# NFC_Business_Card_2024_Jan_06.net
KiCad netlist of a schematic drawn in EasyEDA
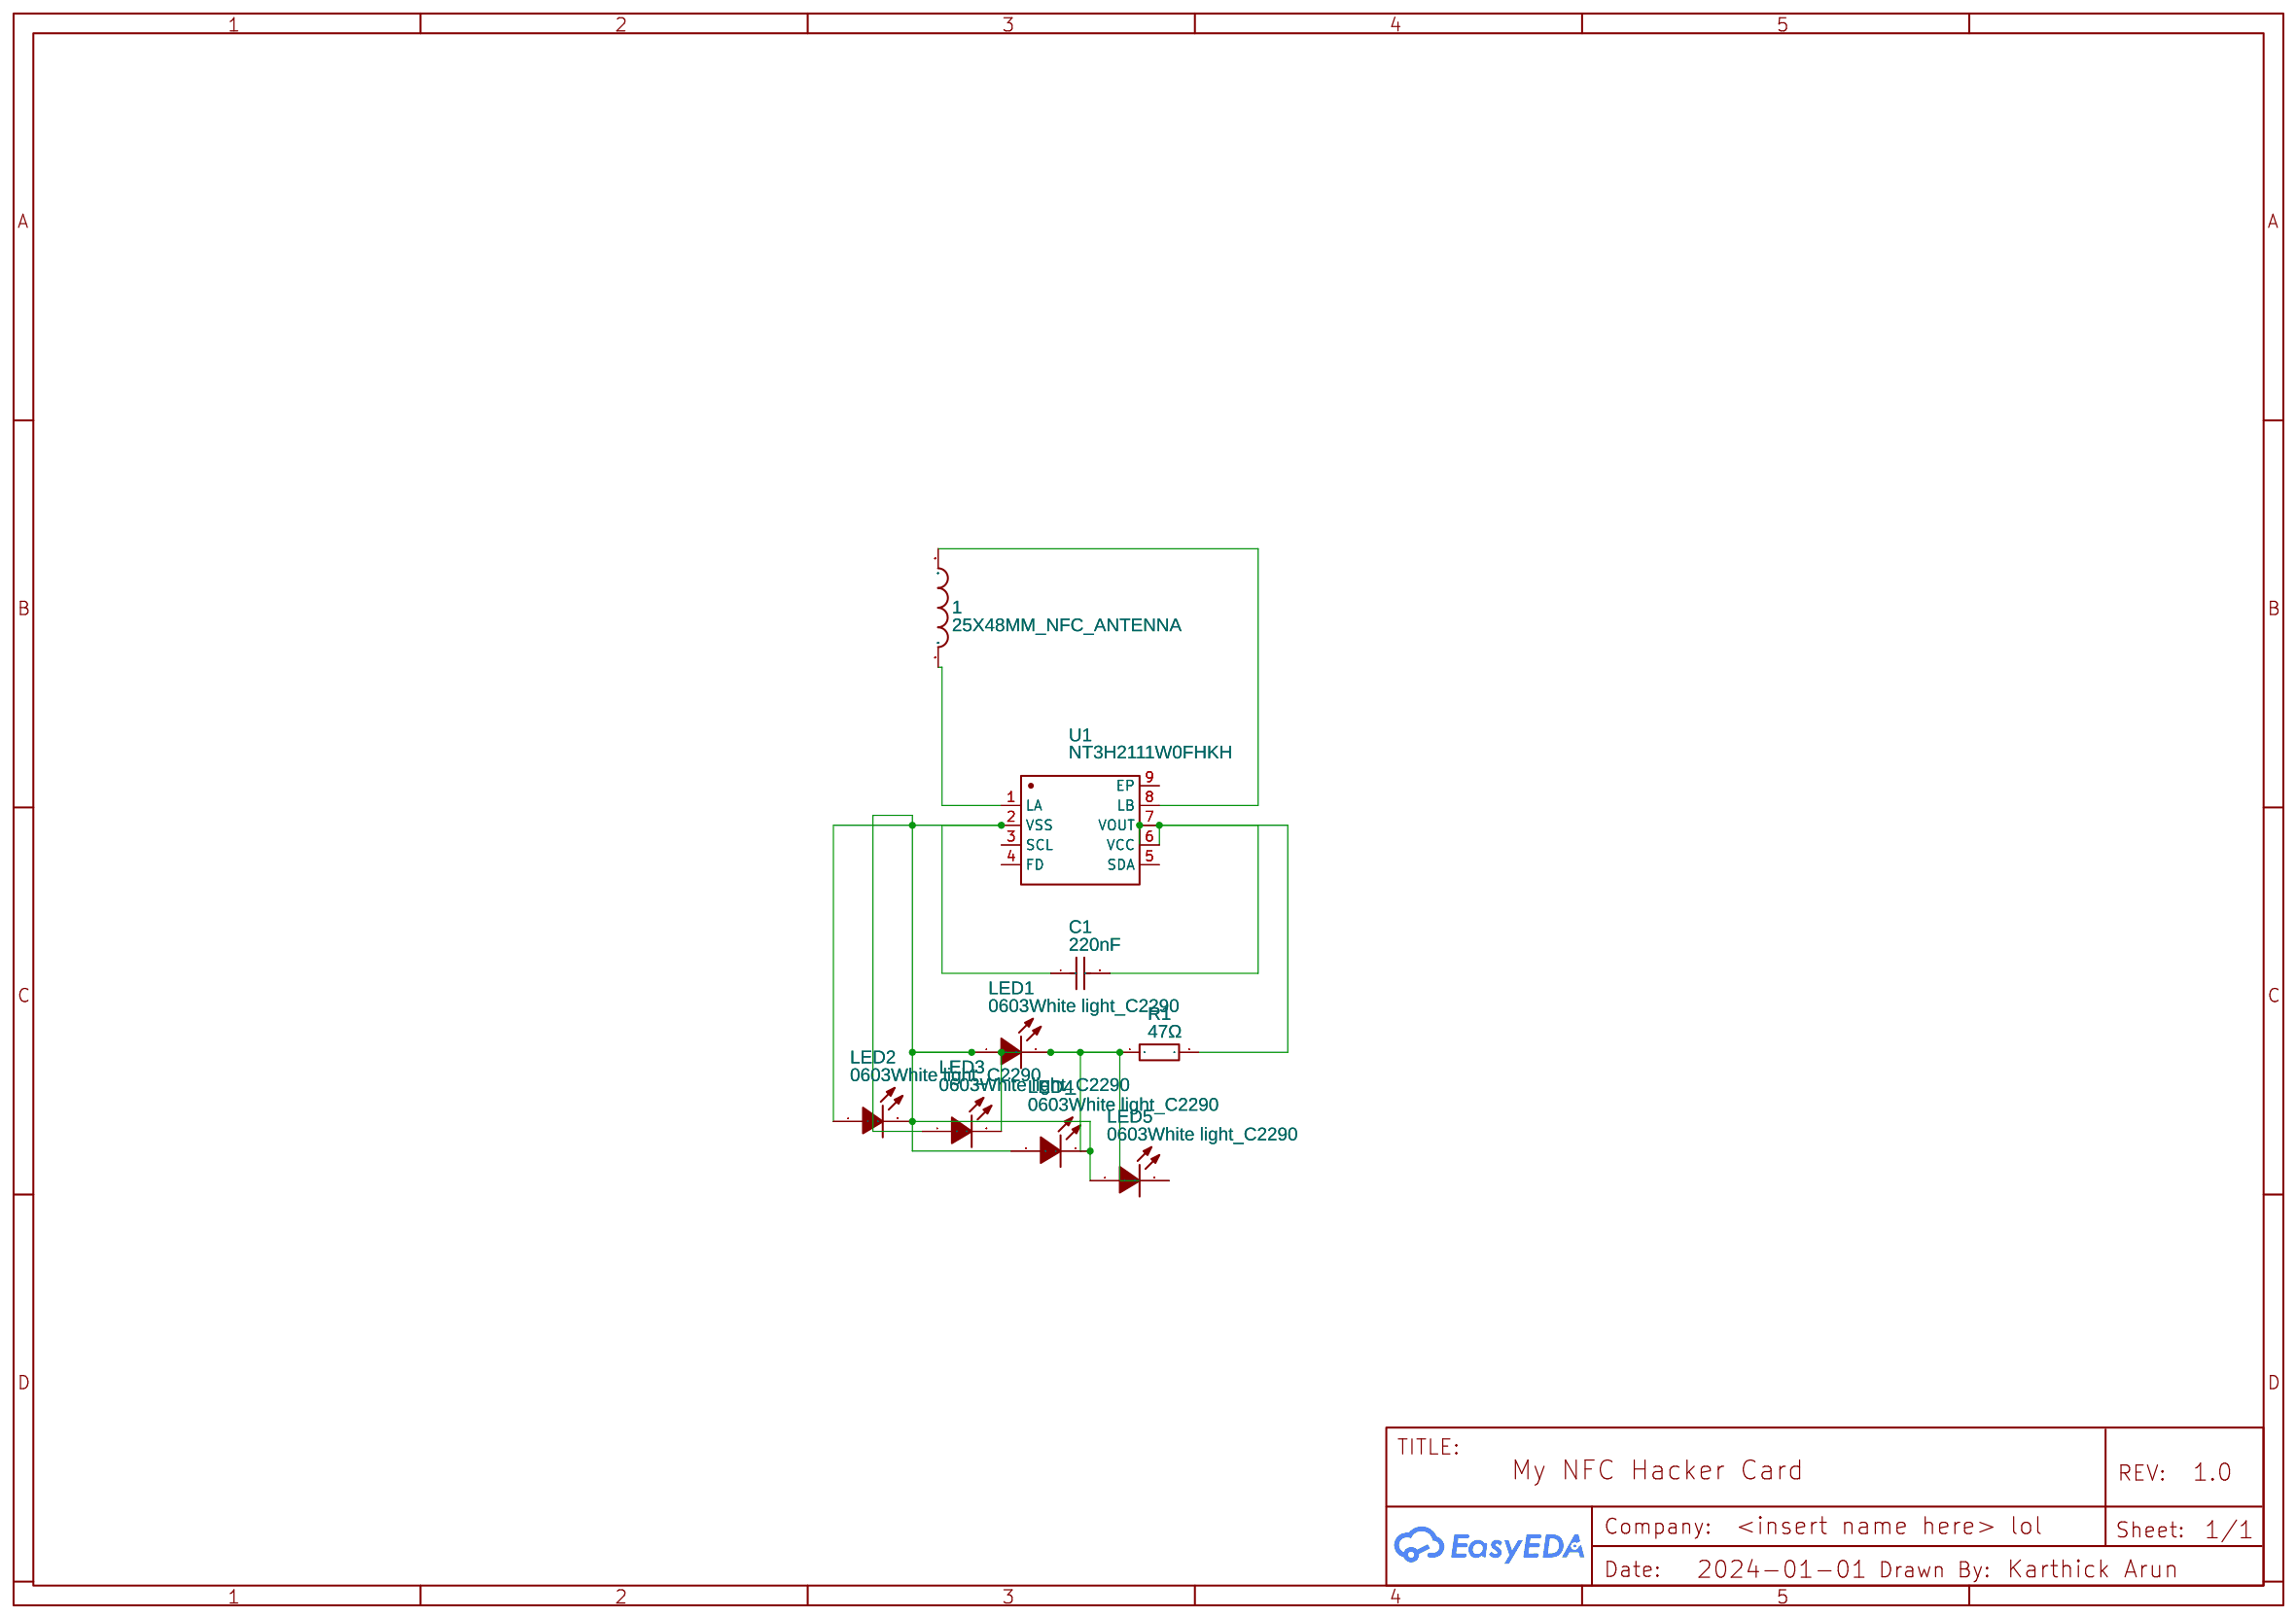
[diagram p0: schematic sheet]

(export (version "E")
  (design (tool "Eeschema 10.0.6"))
  (components
    (comp (ref "1") (value "25X48MM_NFC_ANTENNA") (libsource (lib "") (part "25X48MM_NFC_ANTENNA")))
    (comp (ref "C1")
      (value "220nF")
      (fields
        (field (name "Manufacturer Part") "CL10B224KA8NNNC")
        (field (name "Manufacturer") "SAMSUNG(三星)")
      )
      (libsource (lib "") (part "CL10B224KA8NNNC"))
    )
    (comp (ref "LED1")
      (value "0603White light_C2290")
      (fields (field (name "Manufacturer Part") "KT-0603白灯") (field (name "Manufacturer") "KENTO"))
      (libsource (lib "") (part "0603White light_C2290"))
    )
    (comp (ref "LED2")
      (value "0603White light_C2290")
      (fields (field (name "Manufacturer Part") "KT-0603白灯") (field (name "Manufacturer") "KENTO"))
      (libsource (lib "") (part "0603White light_C2290"))
    )
    (comp (ref "LED3")
      (value "0603White light_C2290")
      (fields (field (name "Manufacturer Part") "KT-0603白灯") (field (name "Manufacturer") "KENTO"))
      (libsource (lib "") (part "0603White light_C2290"))
    )
    (comp (ref "LED4")
      (value "0603White light_C2290")
      (fields (field (name "Manufacturer Part") "KT-0603白灯") (field (name "Manufacturer") "KENTO"))
      (libsource (lib "") (part "0603White light_C2290"))
    )
    (comp (ref "LED5")
      (value "0603White light_C2290")
      (fields (field (name "Manufacturer Part") "KT-0603白灯") (field (name "Manufacturer") "KENTO"))
      (libsource (lib "") (part "0603White light_C2290"))
    )
    (comp (ref "R1")
      (value "47Ω")
      (fields
        (field (name "Manufacturer Part") "0603WAF470JT5E")
        (field (name "Manufacturer") "UNI-ROYAL(厚声)")
      )
      (libsource (lib "") (part "0603WAF470JT5E"))
    )
    (comp (ref "U1")
      (value "NT3H2111W0FHKH")
      (fields (field (name "Manufacturer") "NXP(恩智浦)"))
      (libsource (lib "") (part "NT3H2111W0FHKH"))
    )
  )
  (nets
    (net (code "1") (name "Net-(LED1-A)") (class "Default")
      (node (ref "C1") (pin "1") (pinfunction "1_1") (pintype "input"))
      (node (ref "LED1") (pin "1") (pinfunction "A_1") (pintype "unspecified"))
      (node (ref "LED1") (pin "2") (pinfunction "K_2") (pintype "unspecified"))
      (node (ref "LED2") (pin "1") (pinfunction "A_1") (pintype "unspecified"))
      (node (ref "LED2") (pin "2") (pinfunction "K_2") (pintype "unspecified"))
      (node (ref "LED3") (pin "1") (pinfunction "A_1") (pintype "unspecified"))
      (node (ref "LED3") (pin "2") (pinfunction "K_2") (pintype "unspecified"))
      (node (ref "LED4") (pin "1") (pinfunction "A_1") (pintype "unspecified"))
      (node (ref "LED4") (pin "2") (pinfunction "K_2") (pintype "unspecified"))
      (node (ref "LED5") (pin "1") (pinfunction "A_1") (pintype "unspecified"))
      (node (ref "LED5") (pin "2") (pinfunction "K_2") (pintype "unspecified"))
      (node (ref "R1") (pin "1") (pinfunction "1_1") (pintype "input"))
      (node (ref "U1") (pin "2") (pinfunction "VSS_2") (pintype "unspecified"))
    )
    (net (code "2") (name "Net-(U1-LA)") (class "Default")
      (node (ref "1") (pin "P$2") (pinfunction "P$2_P$2") (pintype "bidirectional"))
      (node (ref "U1") (pin "1") (pinfunction "LA_1") (pintype "unspecified"))
    )
    (net (code "3") (name "Net-(U1-LB)") (class "Default")
      (node (ref "1") (pin "P$1") (pinfunction "P$1_P$1") (pintype "bidirectional"))
      (node (ref "U1") (pin "8") (pinfunction "LB_8") (pintype "unspecified"))
    )
    (net (code "4") (name "Net-(U1-VCC)") (class "Default")
      (node (ref "C1") (pin "2") (pinfunction "2_2") (pintype "input"))
      (node (ref "R1") (pin "2") (pinfunction "2_2") (pintype "input"))
      (node (ref "U1") (pin "6") (pinfunction "VCC_6") (pintype "unspecified"))
      (node (ref "U1") (pin "7") (pinfunction "VOUT_7") (pintype "unspecified"))
    )
    (net (code "5") (name "unconnected-(U1-EP-Pad9)") (class "Default")
      (node (ref "U1") (pin "9") (pinfunction "EP_9") (pintype "unspecified"))
    )
    (net (code "6") (name "unconnected-(U1-FD-Pad4)") (class "Default")
      (node (ref "U1") (pin "4") (pinfunction "FD_4") (pintype "unspecified"))
    )
    (net (code "7") (name "unconnected-(U1-SCL-Pad3)") (class "Default")
      (node (ref "U1") (pin "3") (pinfunction "SCL_3") (pintype "unspecified"))
    )
    (net (code "8") (name "unconnected-(U1-SDA-Pad5)") (class "Default")
      (node (ref "U1") (pin "5") (pinfunction "SDA_5") (pintype "unspecified"))
    )
  )
)
